# Controller_PCB_Base.net
KiCad netlist of a schematic drawn in Altium Designer
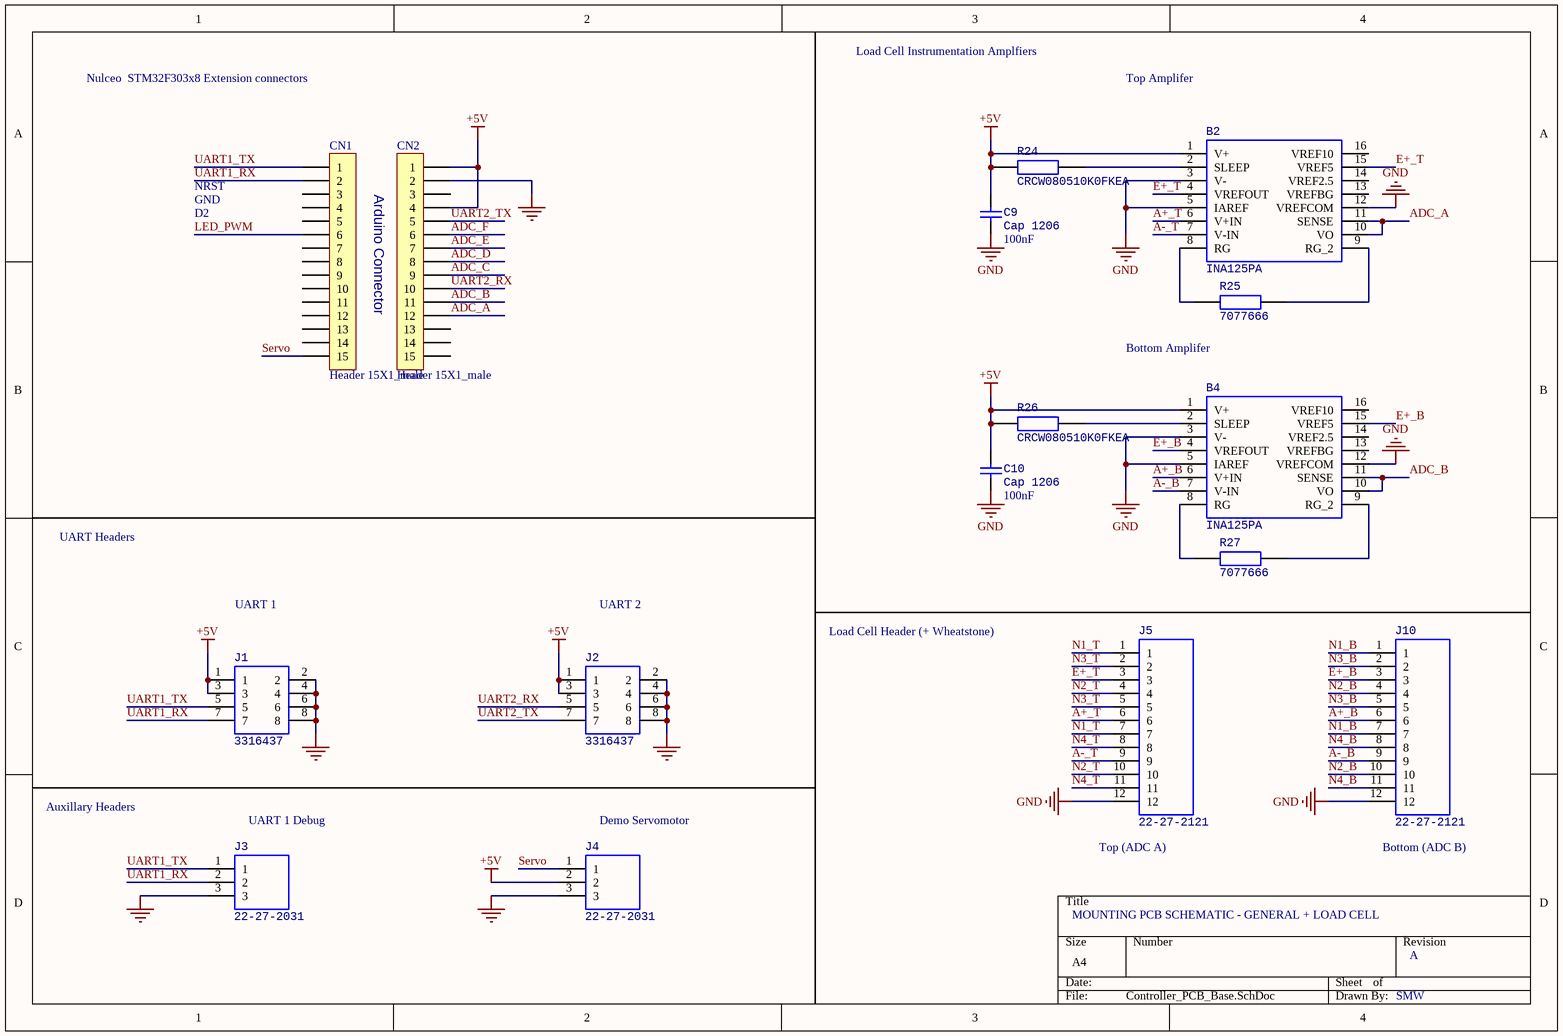
[diagram p0: Controller_PCB_Base.SchDoc]

(export (version "E")
  (design (tool "Eeschema 10.0.6"))
  (components
    (comp (ref "B2")
      (value "INA125PA")
      (footprint "DIP254P762X508-16")
      (description "Instrumentation Amplifier with Precision Voltage Reference")
      (fields (field (name "RS PART NUMBER") "2521593P"))
      (libsource (lib "INA125PA") (part "INA125PA"))
    )
    (comp (ref "B4")
      (value "INA125PA")
      (footprint "DIP254P762X508-16")
      (description "Instrumentation Amplifier with Precision Voltage Reference")
      (fields (field (name "RS PART NUMBER") "2521593P"))
      (libsource (lib "INA125PA") (part "INA125PA"))
    )
    (comp (ref "C9")
      (value "Cap 1206")
      (footprint "C1206")
      (description "Capacitor (Semiconductor SIM Model)")
      (fields (field (name "ALTIUM_VALUE") "100nF") (field (name "PUBLISHER") "Altium Limited"))
      (libsource (lib "Miscellaneous Devices") (part "Cap Semi"))
    )
    (comp (ref "C10")
      (value "Cap 1206")
      (footprint "C1206")
      (description "Capacitor (Semiconductor SIM Model)")
      (fields (field (name "ALTIUM_VALUE") "100nF") (field (name "PUBLISHER") "Altium Limited"))
      (libsource (lib "Miscellaneous Devices") (part "Cap Semi"))
    )
    (comp (ref "CN1")
      (value "Header 15X1_male")
      (footprint "HDR_1x15_2R54_V_F")
      (description "Header, 10-Pin, Single row,female")
      (fields (field (name "PUBLISHER") "Altium Limited"))
      (libsource (lib "MB1180") (part "Header 15X1_Female_1"))
    )
    (comp (ref "CN2")
      (value "Header 15X1_male")
      (footprint "HDR_1x15_2R54_V_F")
      (description "Header, 10-Pin, Single row,female")
      (fields (field (name "PUBLISHER") "Altium Limited"))
      (libsource (lib "") (part "Header 15X1_Female_1_1"))
    )
    (comp (ref "J1") (value "3316437") (footprint "RJ45-8") (libsource (lib "3316437") (part "3316437")))
    (comp (ref "J2") (value "3316437") (footprint "RJ45-8") (libsource (lib "3316437") (part "3316437")))
    (comp (ref "J3")
      (value "22-27-2031")
      (footprint "SHDR3W64P0X254_1X3_762X580X1170P")
      (fields (field (name "RS PART NUMBER") "1707102"))
      (libsource (lib "22-27-2031") (part "22-27-2031"))
    )
    (comp (ref "J4")
      (value "22-27-2031")
      (footprint "SHDR3W64P0X254_1X3_762X580X1170P")
      (fields (field (name "RS PART NUMBER") "1707102"))
      (libsource (lib "22-27-2031") (part "22-27-2031"))
    )
    (comp (ref "J5")
      (value "22-27-2121")
      (footprint "HDRV12W64P0X254_1X12_3048X580X1170P")
      (fields (field (name "RS PART NUMBER") "1707108"))
      (libsource (lib "22-27-2121") (part "22-27-2121"))
    )
    (comp (ref "J10")
      (value "22-27-2121")
      (footprint "HDRV12W64P0X254_1X12_3048X580X1170P")
      (fields (field (name "RS PART NUMBER") "1707108"))
      (libsource (lib "22-27-2121") (part "22-27-2121"))
    )
    (comp (ref "R24")
      (value "CRCW080510K0FKEA")
      (footprint "RESC2012X50N")
      (fields (field (name "RS PART NUMBER") "1694499"))
      (libsource (lib "CRCW080510K0FKEA") (part "CRCW080510K0FKEA"))
    )
    (comp (ref "R25")
      (value "7077666")
      (footprint "RESAD1550W58L630D230")
      (description "RS Pro RS Series Axial Carbon Resistor 1k 5% 0.25W -500  +350ppm/C")
      (libsource (lib "7077666") (part "7077666"))
    )
    (comp (ref "R26")
      (value "CRCW080510K0FKEA")
      (footprint "RESC2012X50N")
      (fields (field (name "RS PART NUMBER") "1694499"))
      (libsource (lib "CRCW080510K0FKEA") (part "CRCW080510K0FKEA"))
    )
    (comp (ref "R27")
      (value "7077666")
      (footprint "RESAD1550W58L630D230")
      (description "RS Pro RS Series Axial Carbon Resistor 1k 5% 0.25W -500  +350ppm/C")
      (libsource (lib "7077666") (part "7077666"))
    )
  )
  (nets
    (net (code "1") (name "+5V") (class "Default")
      (node (ref "B2") (pin "1") (pinfunction "V+_1") (pintype "passive"))
      (node (ref "B4") (pin "1") (pinfunction "V+_1") (pintype "passive"))
      (node (ref "C10") (pin "2") (pinfunction "2_2") (pintype "passive"))
      (node (ref "C9") (pin "2") (pinfunction "2_2") (pintype "passive"))
      (node (ref "CN2") (pin "1") (pinfunction "1_1") (pintype "passive"))
      (node (ref "CN2") (pin "4") (pinfunction "4_4") (pintype "passive"))
      (node (ref "J1") (pin "1") (pinfunction "1_1") (pintype "passive"))
      (node (ref "J1") (pin "3") (pinfunction "3_3") (pintype "passive"))
      (node (ref "J2") (pin "1") (pinfunction "1_1") (pintype "passive"))
      (node (ref "J2") (pin "3") (pinfunction "3_3") (pintype "passive"))
      (node (ref "J4") (pin "2") (pinfunction "2_2") (pintype "passive"))
      (node (ref "R24") (pin "1") (pinfunction "1_1") (pintype "passive"))
      (node (ref "R26") (pin "1") (pinfunction "1_1") (pintype "passive"))
    )
    (net (code "2") (name "/A+_B") (class "Default")
      (node (ref "B4") (pin "6") (pinfunction "V+IN_6") (pintype "passive"))
      (node (ref "J10") (pin "6") (pinfunction "6_6") (pintype "passive"))
    )
    (net (code "3") (name "/A+_T") (class "Default")
      (node (ref "B2") (pin "6") (pinfunction "V+IN_6") (pintype "passive"))
      (node (ref "J5") (pin "6") (pinfunction "6_6") (pintype "passive"))
    )
    (net (code "4") (name "/A-_B") (class "Default")
      (node (ref "B4") (pin "7") (pinfunction "V-IN_7") (pintype "passive"))
      (node (ref "J10") (pin "9") (pinfunction "9_9") (pintype "passive"))
    )
    (net (code "5") (name "/A-_T") (class "Default")
      (node (ref "B2") (pin "7") (pinfunction "V-IN_7") (pintype "passive"))
      (node (ref "J5") (pin "9") (pinfunction "9_9") (pintype "passive"))
    )
    (net (code "6") (name "/ADC_A") (class "Default")
      (node (ref "B2") (pin "10") (pinfunction "VO_10") (pintype "passive"))
      (node (ref "B2") (pin "11") (pinfunction "SENSE_11") (pintype "passive"))
      (node (ref "CN2") (pin "12") (pinfunction "12_12") (pintype "passive"))
    )
    (net (code "7") (name "/ADC_B") (class "Default")
      (node (ref "B4") (pin "10") (pinfunction "VO_10") (pintype "passive"))
      (node (ref "B4") (pin "11") (pinfunction "SENSE_11") (pintype "passive"))
      (node (ref "CN2") (pin "11") (pinfunction "11_11") (pintype "passive"))
    )
    (net (code "8") (name "/ADC_C") (class "Default")
      (node (ref "CN2") (pin "9") (pinfunction "9_9") (pintype "passive"))
    )
    (net (code "9") (name "/ADC_D") (class "Default")
      (node (ref "CN2") (pin "8") (pinfunction "8_8") (pintype "passive"))
    )
    (net (code "10") (name "/ADC_E") (class "Default")
      (node (ref "CN2") (pin "7") (pinfunction "7_7") (pintype "passive"))
    )
    (net (code "11") (name "/ADC_F") (class "Default")
      (node (ref "CN2") (pin "6") (pinfunction "6_6") (pintype "passive"))
    )
    (net (code "12") (name "/E+_B") (class "Default")
      (node (ref "B4") (pin "15") (pinfunction "VREF5_15") (pintype "passive"))
      (node (ref "B4") (pin "4") (pinfunction "VREFOUT_4") (pintype "passive"))
      (node (ref "J10") (pin "3") (pinfunction "3_3") (pintype "passive"))
    )
    (net (code "13") (name "/E+_T") (class "Default")
      (node (ref "B2") (pin "15") (pinfunction "VREF5_15") (pintype "passive"))
      (node (ref "B2") (pin "4") (pinfunction "VREFOUT_4") (pintype "passive"))
      (node (ref "J5") (pin "3") (pinfunction "3_3") (pintype "passive"))
    )
    (net (code "14") (name "/LED_PWM") (class "Default")
      (node (ref "CN1") (pin "6") (pinfunction "6_6") (pintype "passive"))
    )
    (net (code "15") (name "/N1_B") (class "Default")
      (node (ref "J10") (pin "1") (pinfunction "1_1") (pintype "passive"))
      (node (ref "J10") (pin "7") (pinfunction "7_7") (pintype "passive"))
    )
    (net (code "16") (name "/N1_T") (class "Default")
      (node (ref "J5") (pin "1") (pinfunction "1_1") (pintype "passive"))
      (node (ref "J5") (pin "7") (pinfunction "7_7") (pintype "passive"))
    )
    (net (code "17") (name "/N2_B") (class "Default")
      (node (ref "J10") (pin "10") (pinfunction "10_10") (pintype "passive"))
      (node (ref "J10") (pin "4") (pinfunction "4_4") (pintype "passive"))
    )
    (net (code "18") (name "/N2_T") (class "Default")
      (node (ref "J5") (pin "10") (pinfunction "10_10") (pintype "passive"))
      (node (ref "J5") (pin "4") (pinfunction "4_4") (pintype "passive"))
    )
    (net (code "19") (name "/N3_B") (class "Default")
      (node (ref "J10") (pin "2") (pinfunction "2_2") (pintype "passive"))
      (node (ref "J10") (pin "5") (pinfunction "5_5") (pintype "passive"))
    )
    (net (code "20") (name "/N3_T") (class "Default")
      (node (ref "J5") (pin "2") (pinfunction "2_2") (pintype "passive"))
      (node (ref "J5") (pin "5") (pinfunction "5_5") (pintype "passive"))
    )
    (net (code "21") (name "/N4_B") (class "Default")
      (node (ref "J10") (pin "11") (pinfunction "11_11") (pintype "passive"))
      (node (ref "J10") (pin "8") (pinfunction "8_8") (pintype "passive"))
    )
    (net (code "22") (name "/N4_T") (class "Default")
      (node (ref "J5") (pin "11") (pinfunction "11_11") (pintype "passive"))
      (node (ref "J5") (pin "8") (pinfunction "8_8") (pintype "passive"))
    )
    (net (code "23") (name "/Servo") (class "Default")
      (node (ref "CN1") (pin "15") (pinfunction "15_15") (pintype "passive"))
      (node (ref "J4") (pin "1") (pinfunction "1_1") (pintype "passive"))
    )
    (net (code "24") (name "/UART1_RX") (class "Default")
      (node (ref "CN1") (pin "2") (pinfunction "2_2") (pintype "passive"))
      (node (ref "J1") (pin "7") (pinfunction "7_7") (pintype "passive"))
      (node (ref "J3") (pin "2") (pinfunction "2_2") (pintype "passive"))
    )
    (net (code "25") (name "/UART1_TX") (class "Default")
      (node (ref "CN1") (pin "1") (pinfunction "1_1") (pintype "passive"))
      (node (ref "J1") (pin "5") (pinfunction "5_5") (pintype "passive"))
      (node (ref "J3") (pin "1") (pinfunction "1_1") (pintype "passive"))
    )
    (net (code "26") (name "/UART2_RX") (class "Default")
      (node (ref "CN2") (pin "10") (pinfunction "10_10") (pintype "passive"))
      (node (ref "J2") (pin "5") (pinfunction "5_5") (pintype "passive"))
    )
    (net (code "27") (name "/UART2_TX") (class "Default")
      (node (ref "CN2") (pin "5") (pinfunction "5_5") (pintype "passive"))
      (node (ref "J2") (pin "7") (pinfunction "7_7") (pintype "passive"))
    )
    (net (code "28") (name "GND") (class "Default")
      (node (ref "B2") (pin "12") (pinfunction "VREFCOM_12") (pintype "passive"))
      (node (ref "B2") (pin "3") (pinfunction "V-_3") (pintype "passive"))
      (node (ref "B2") (pin "5") (pinfunction "IAREF_5") (pintype "passive"))
      (node (ref "B4") (pin "12") (pinfunction "VREFCOM_12") (pintype "passive"))
      (node (ref "B4") (pin "3") (pinfunction "V-_3") (pintype "passive"))
      (node (ref "B4") (pin "5") (pinfunction "IAREF_5") (pintype "passive"))
      (node (ref "C10") (pin "1") (pinfunction "1_1") (pintype "passive"))
      (node (ref "C9") (pin "1") (pinfunction "1_1") (pintype "passive"))
      (node (ref "CN2") (pin "2") (pinfunction "2_2") (pintype "passive"))
      (node (ref "J1") (pin "2") (pinfunction "2_2") (pintype "passive"))
      (node (ref "J1") (pin "4") (pinfunction "4_4") (pintype "passive"))
      (node (ref "J1") (pin "6") (pinfunction "6_6") (pintype "passive"))
      (node (ref "J1") (pin "8") (pinfunction "8_8") (pintype "passive"))
      (node (ref "J10") (pin "12") (pinfunction "12_12") (pintype "passive"))
      (node (ref "J2") (pin "2") (pinfunction "2_2") (pintype "passive"))
      (node (ref "J2") (pin "4") (pinfunction "4_4") (pintype "passive"))
      (node (ref "J2") (pin "6") (pinfunction "6_6") (pintype "passive"))
      (node (ref "J2") (pin "8") (pinfunction "8_8") (pintype "passive"))
      (node (ref "J3") (pin "3") (pinfunction "3_3") (pintype "passive"))
      (node (ref "J4") (pin "3") (pinfunction "3_3") (pintype "passive"))
      (node (ref "J5") (pin "12") (pinfunction "12_12") (pintype "passive"))
    )
    (net (code "29") (name "Net-(B2-RG)") (class "Default")
      (node (ref "B2") (pin "8") (pinfunction "RG_8") (pintype "passive"))
      (node (ref "R25") (pin "1") (pinfunction "1_1") (pintype "passive"))
    )
    (net (code "30") (name "Net-(B2-RG_2)") (class "Default")
      (node (ref "B2") (pin "9") (pinfunction "RG_2_9") (pintype "passive"))
      (node (ref "R25") (pin "2") (pinfunction "2_2") (pintype "passive"))
    )
    (net (code "31") (name "Net-(B2-SLEEP)") (class "Default")
      (node (ref "B2") (pin "2") (pinfunction "SLEEP_2") (pintype "passive"))
      (node (ref "R24") (pin "2") (pinfunction "2_2") (pintype "passive"))
    )
    (net (code "32") (name "Net-(B4-RG)") (class "Default")
      (node (ref "B4") (pin "8") (pinfunction "RG_8") (pintype "passive"))
      (node (ref "R27") (pin "1") (pinfunction "1_1") (pintype "passive"))
    )
    (net (code "33") (name "Net-(B4-RG_2)") (class "Default")
      (node (ref "B4") (pin "9") (pinfunction "RG_2_9") (pintype "passive"))
      (node (ref "R27") (pin "2") (pinfunction "2_2") (pintype "passive"))
    )
    (net (code "34") (name "Net-(B4-SLEEP)") (class "Default")
      (node (ref "B4") (pin "2") (pinfunction "SLEEP_2") (pintype "passive"))
      (node (ref "R26") (pin "2") (pinfunction "2_2") (pintype "passive"))
    )
    (net (code "35") (name "unconnected-(B2-VREF2.5-Pad14)") (class "Default")
      (node (ref "B2") (pin "14") (pinfunction "VREF2.5_14") (pintype "passive"))
    )
    (net (code "36") (name "unconnected-(B2-VREF10-Pad16)") (class "Default")
      (node (ref "B2") (pin "16") (pinfunction "VREF10_16") (pintype "passive"))
    )
    (net (code "37") (name "unconnected-(B2-VREFBG-Pad13)") (class "Default")
      (node (ref "B2") (pin "13") (pinfunction "VREFBG_13") (pintype "passive"))
    )
    (net (code "38") (name "unconnected-(B4-VREF2.5-Pad14)") (class "Default")
      (node (ref "B4") (pin "14") (pinfunction "VREF2.5_14") (pintype "passive"))
    )
    (net (code "39") (name "unconnected-(B4-VREF10-Pad16)") (class "Default")
      (node (ref "B4") (pin "16") (pinfunction "VREF10_16") (pintype "passive"))
    )
    (net (code "40") (name "unconnected-(B4-VREFBG-Pad13)") (class "Default")
      (node (ref "B4") (pin "13") (pinfunction "VREFBG_13") (pintype "passive"))
    )
    (net (code "41") (name "unconnected-(CN1-Pad3)") (class "Default")
      (node (ref "CN1") (pin "3") (pinfunction "3_3") (pintype "passive"))
    )
    (net (code "42") (name "unconnected-(CN1-Pad4)") (class "Default")
      (node (ref "CN1") (pin "4") (pinfunction "4_4") (pintype "passive"))
    )
    (net (code "43") (name "unconnected-(CN1-Pad5)") (class "Default")
      (node (ref "CN1") (pin "5") (pinfunction "5_5") (pintype "passive"))
    )
    (net (code "44") (name "unconnected-(CN1-Pad7)") (class "Default")
      (node (ref "CN1") (pin "7") (pinfunction "7_7") (pintype "passive"))
    )
    (net (code "45") (name "unconnected-(CN1-Pad8)") (class "Default")
      (node (ref "CN1") (pin "8") (pinfunction "8_8") (pintype "passive"))
    )
    (net (code "46") (name "unconnected-(CN1-Pad9)") (class "Default")
      (node (ref "CN1") (pin "9") (pinfunction "9_9") (pintype "passive"))
    )
    (net (code "47") (name "unconnected-(CN1-Pad10)") (class "Default")
      (node (ref "CN1") (pin "10") (pinfunction "10_10") (pintype "passive"))
    )
    (net (code "48") (name "unconnected-(CN1-Pad11)") (class "Default")
      (node (ref "CN1") (pin "11") (pinfunction "11_11") (pintype "passive"))
    )
    (net (code "49") (name "unconnected-(CN1-Pad12)") (class "Default")
      (node (ref "CN1") (pin "12") (pinfunction "12_12") (pintype "passive"))
    )
    (net (code "50") (name "unconnected-(CN1-Pad13)") (class "Default")
      (node (ref "CN1") (pin "13") (pinfunction "13_13") (pintype "passive"))
    )
    (net (code "51") (name "unconnected-(CN1-Pad14)") (class "Default")
      (node (ref "CN1") (pin "14") (pinfunction "14_14") (pintype "passive"))
    )
    (net (code "52") (name "unconnected-(CN2-Pad3)") (class "Default")
      (node (ref "CN2") (pin "3") (pinfunction "3_3") (pintype "passive"))
    )
    (net (code "53") (name "unconnected-(CN2-Pad13)") (class "Default")
      (node (ref "CN2") (pin "13") (pinfunction "13_13") (pintype "passive"))
    )
    (net (code "54") (name "unconnected-(CN2-Pad14)") (class "Default")
      (node (ref "CN2") (pin "14") (pinfunction "14_14") (pintype "passive"))
    )
    (net (code "55") (name "unconnected-(CN2-Pad15)") (class "Default")
      (node (ref "CN2") (pin "15") (pinfunction "15_15") (pintype "passive"))
    )
  )
)
